# ArduitsyR4.net
KiCad netlist of a schematic drawn in EAGLE
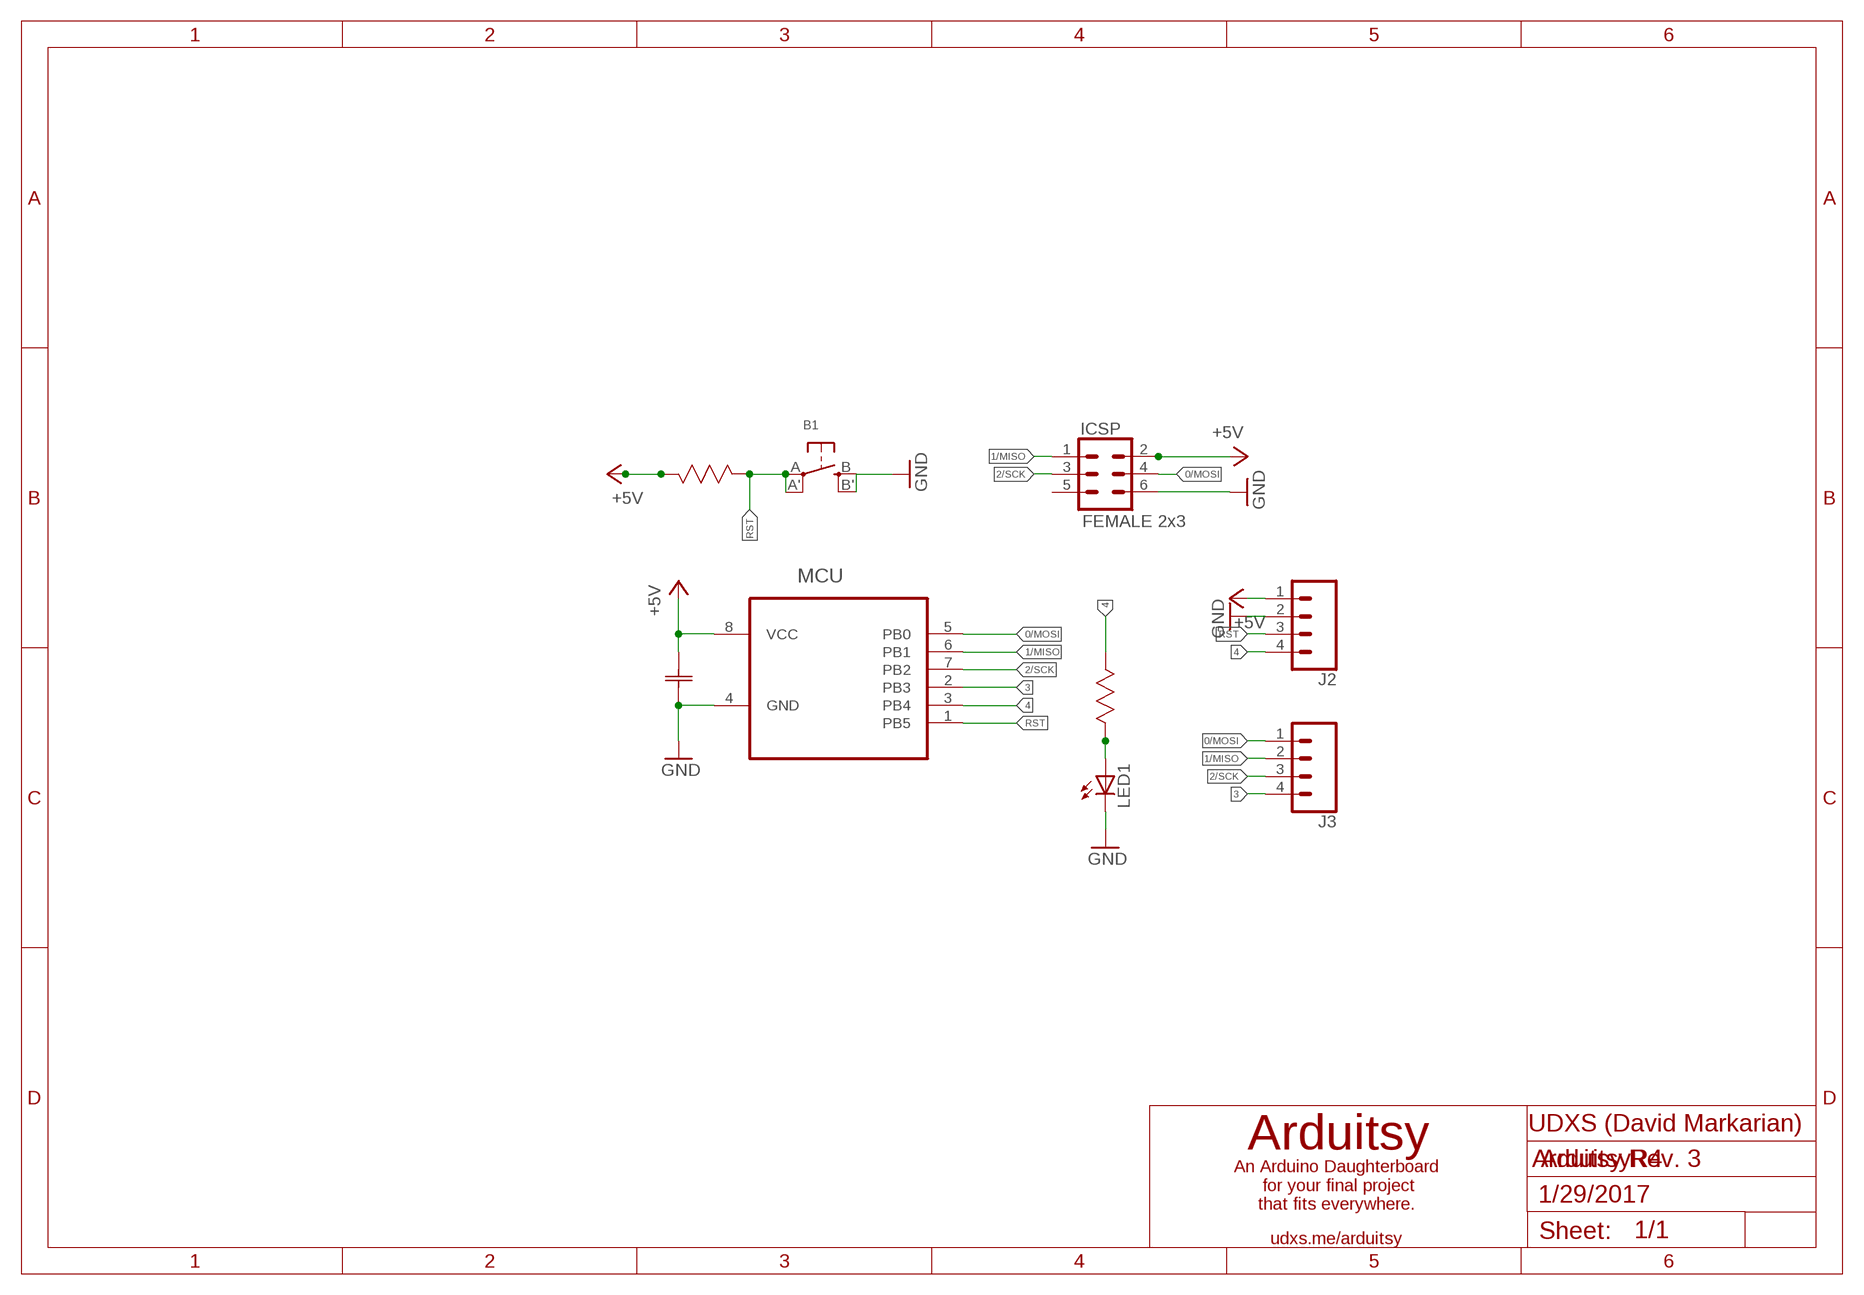
[diagram p0: schematic, sheet 1]

(export (version "E")
  (design (tool "Eeschema 10.0.6"))
  (components
    (comp (ref "B1")
      (value "SWITCH_TACT_SMT")
      (footprint "eagle-import:EVQ-Q2")
      (libsource (lib "eagle-import") (part "SWITCH_TACT_SMT"))
    )
    (comp (ref "C1")
      (value "0.1µF")
      (footprint "eagle-import:CAPC2012X94N")
      (fields (field (name "MPN") "0805YC104KAT4A") (field (name "TOLERANCE") "±10%"))
      (libsource (lib "eagle-import") (part "0805YC104KAT4A"))
    )
    (comp (ref "ICSP")
      (value "FEMALE 2x3")
      (footprint "eagle-import:2X3")
      (libsource (lib "eagle-import") (part "CONN_03X2FEMALE"))
    )
    (comp (ref "J2")
      (value "CONN_04")
      (footprint "eagle-import:1X04")
      (libsource (lib "eagle-import") (part "CONN_04"))
    )
    (comp (ref "J3")
      (value "CONN_04")
      (footprint "eagle-import:1X04")
      (libsource (lib "eagle-import") (part "CONN_04"))
    )
    (comp (ref "LED1")
      (value "LEDCHIPLED_0805")
      (footprint "eagle-import:CHIPLED_0805")
      (libsource (lib "eagle-import") (part "LEDCHIPLED_0805"))
    )
    (comp (ref "MCU")
      (value "ATTINY85-20SU")
      (footprint "eagle-import:SOIC127P798X216-8N")
      (libsource (lib "eagle-import") (part "ATTINY85-20SU"))
    )
    (comp (ref "R1")
      (value "10K Ohms")
      (footprint "eagle-import:RESC2013X65N")
      (fields (field (name "MPN") "MC0.1W08051%10K") (field (name "TOLERANCE") "±1%"))
      (libsource (lib "eagle-import") (part "MC0.1W08051%10K"))
    )
    (comp (ref "R2")
      (value "10K Ohms")
      (footprint "eagle-import:RESC2013X65N")
      (fields (field (name "MPN") "MC0.1W08051%10K") (field (name "TOLERANCE") "±1%"))
      (libsource (lib "eagle-import") (part "MC0.1W08051%10K"))
    )
  )
  (nets
    (net (code "1") (name "+5V") (class "Default")
      (node (ref "C1") (pin "1") (pinfunction "C1_1") (pintype "passive"))
      (node (ref "ICSP") (pin "2") (pinfunction "2_2") (pintype "bidirectional"))
      (node (ref "J2") (pin "1") (pinfunction "1_1") (pintype "passive"))
      (node (ref "MCU") (pin "8") (pinfunction "VCC_8") (pintype "power_in"))
      (node (ref "R1") (pin "1") (pinfunction "R1_1") (pintype "passive"))
    )
    (net (code "2") (name "0{slash}MOSI") (class "Default")
      (node (ref "ICSP") (pin "4") (pinfunction "4_4") (pintype "bidirectional"))
      (node (ref "J3") (pin "1") (pinfunction "1_1") (pintype "passive"))
      (node (ref "MCU") (pin "5") (pinfunction "PB0_5") (pintype "bidirectional"))
    )
    (net (code "3") (name "1{slash}MISO") (class "Default")
      (node (ref "ICSP") (pin "1") (pinfunction "1_1") (pintype "bidirectional"))
      (node (ref "J3") (pin "2") (pinfunction "2_2") (pintype "passive"))
      (node (ref "MCU") (pin "6") (pinfunction "PB1_6") (pintype "bidirectional"))
    )
    (net (code "4") (name "2{slash}SCK") (class "Default")
      (node (ref "ICSP") (pin "3") (pinfunction "3_3") (pintype "bidirectional"))
      (node (ref "J3") (pin "3") (pinfunction "3_3") (pintype "passive"))
      (node (ref "MCU") (pin "7") (pinfunction "PB2_7") (pintype "bidirectional"))
    )
    (net (code "5") (name "3") (class "Default")
      (node (ref "J3") (pin "4") (pinfunction "4_4") (pintype "passive"))
      (node (ref "MCU") (pin "2") (pinfunction "PB3_2") (pintype "bidirectional"))
    )
    (net (code "6") (name "4") (class "Default")
      (node (ref "J2") (pin "4") (pinfunction "4_4") (pintype "passive"))
      (node (ref "MCU") (pin "3") (pinfunction "PB4_3") (pintype "bidirectional"))
      (node (ref "R2") (pin "1") (pinfunction "R1_1") (pintype "passive"))
    )
    (net (code "7") (name "GND") (class "Default")
      (node (ref "B1") (pin "B") (pinfunction "S_B") (pintype "passive"))
      (node (ref "B1") (pin "B'") (pinfunction "S1_B'") (pintype "passive"))
      (node (ref "C1") (pin "2") (pinfunction "C2_2") (pintype "passive"))
      (node (ref "ICSP") (pin "6") (pinfunction "6_6") (pintype "bidirectional"))
      (node (ref "J2") (pin "2") (pinfunction "2_2") (pintype "passive"))
      (node (ref "LED1") (pin "C") (pinfunction "C_C") (pintype "passive"))
      (node (ref "MCU") (pin "4") (pinfunction "GND_4") (pintype "passive"))
    )
    (net (code "8") (name "Net-(R2-R2)") (class "Default")
      (node (ref "LED1") (pin "A") (pinfunction "A_A") (pintype "passive"))
      (node (ref "R2") (pin "2") (pinfunction "R2_2") (pintype "passive"))
    )
    (net (code "9") (name "RST") (class "Default")
      (node (ref "B1") (pin "A") (pinfunction "P_A") (pintype "passive"))
      (node (ref "B1") (pin "A'") (pinfunction "P1_A'") (pintype "passive"))
      (node (ref "J2") (pin "3") (pinfunction "3_3") (pintype "passive"))
      (node (ref "MCU") (pin "1") (pinfunction "PB5_1") (pintype "bidirectional"))
      (node (ref "R1") (pin "2") (pinfunction "R2_2") (pintype "passive"))
    )
    (net (code "10") (name "unconnected-(ICSP-Pad5)") (class "Default")
      (node (ref "ICSP") (pin "5") (pinfunction "5_5") (pintype "bidirectional"))
    )
  )
)
